# Schematic.net
KiCad netlist of a schematic drawn in EAGLE
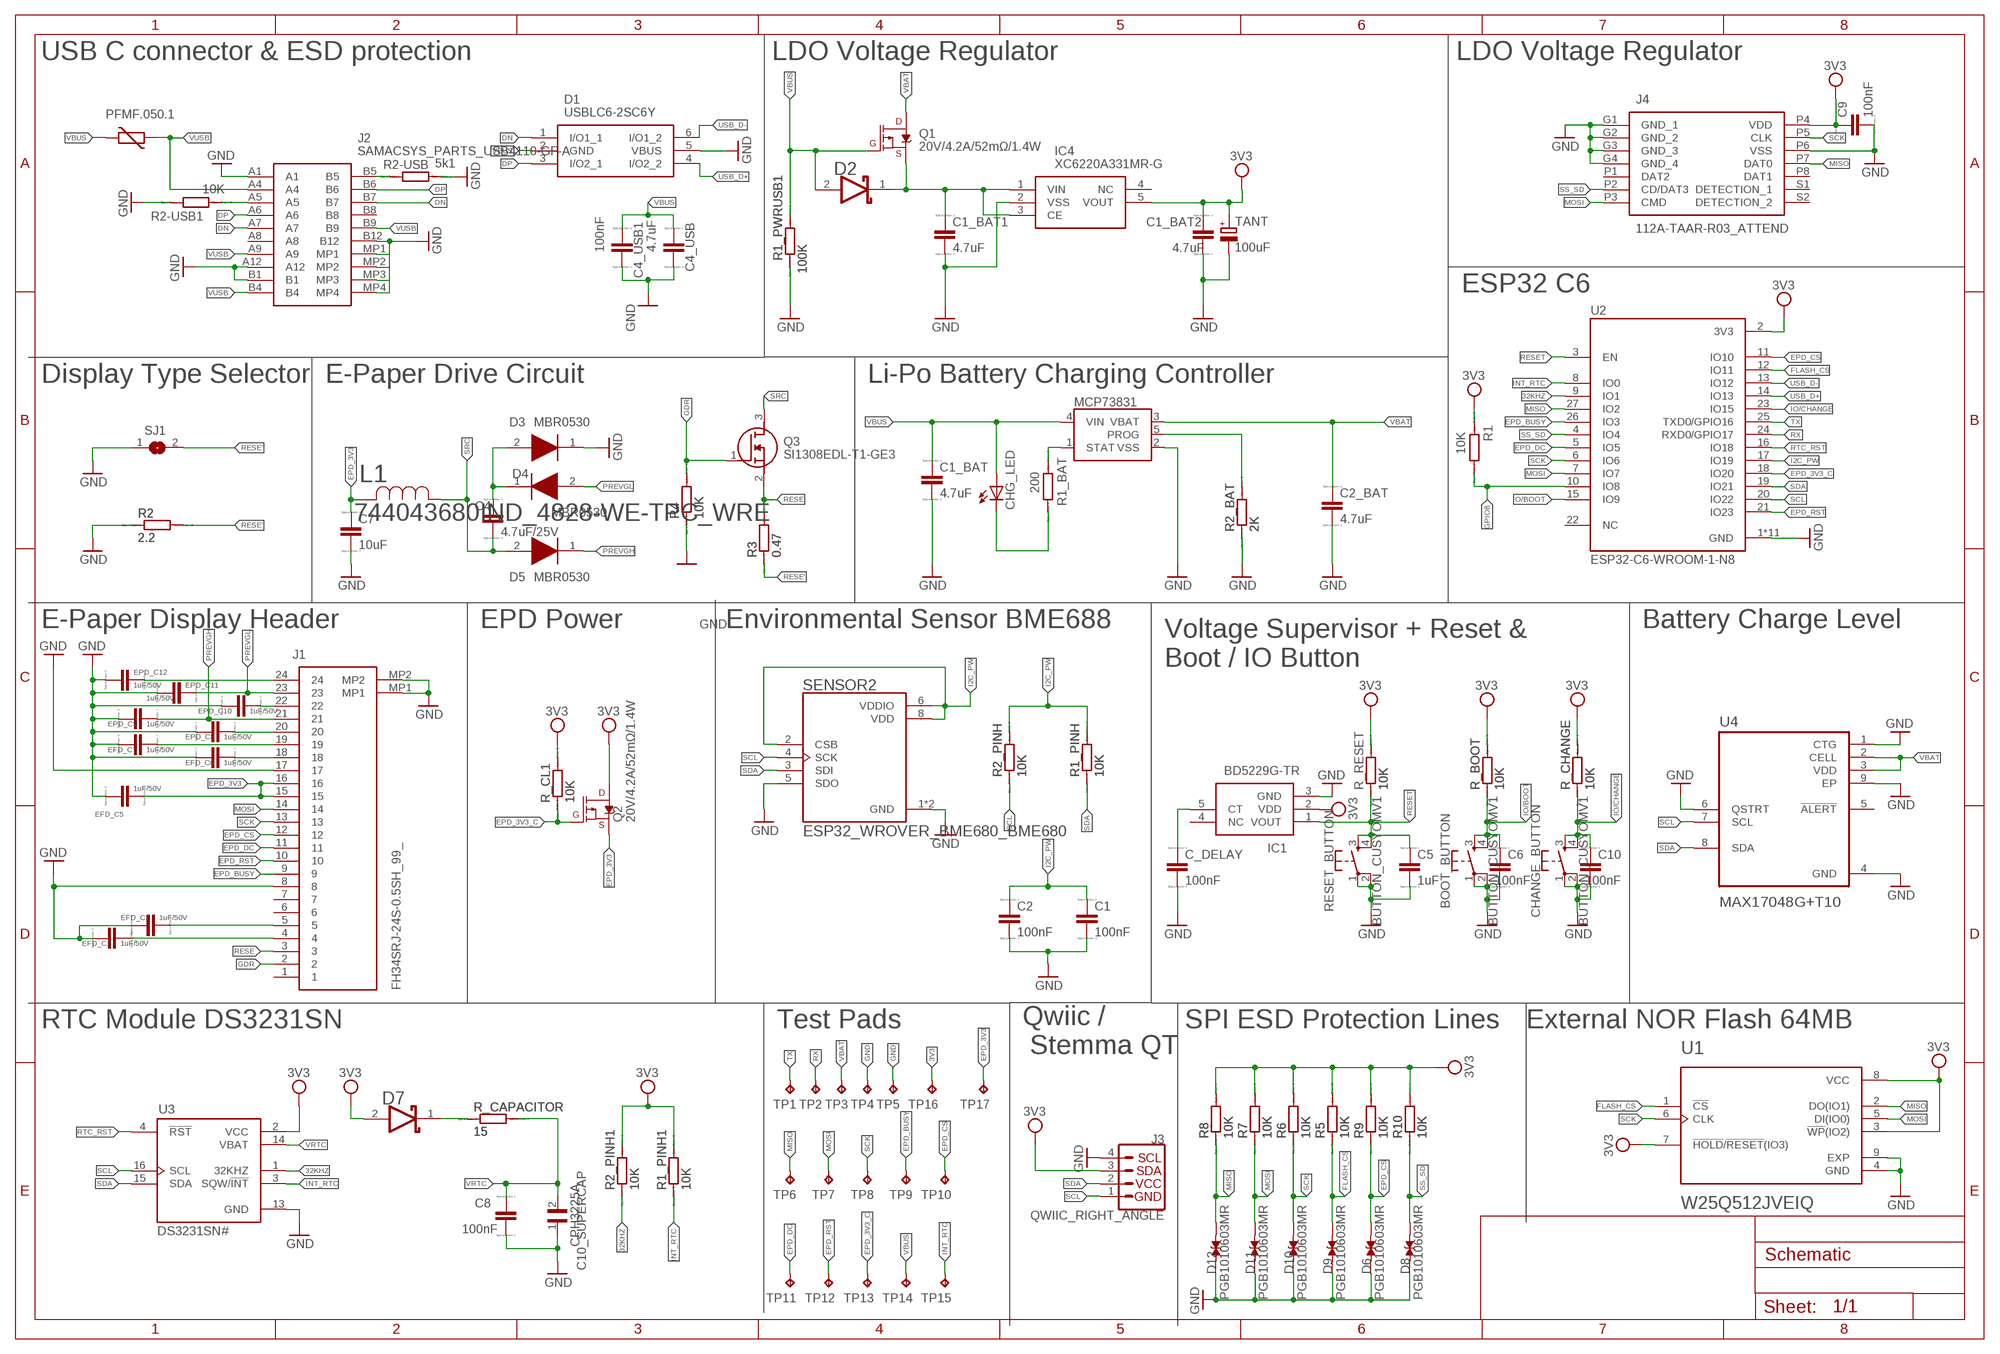
[diagram p0: schematic, sheet 1]

(export (version "E")
  (design (tool "Eeschema 10.0.6"))
  (components
    (comp (ref "BOOT_BUTTON")
      (value "BUTTON_CUSYOMV1")
      (footprint "eagle-import:MYBUTTON")
      (libsource (lib "eagle-import") (part "BUTTON_CUSYOMV1"))
    )
    (comp (ref "C1")
      (value "100nF")
      (footprint "eagle-import:EAGLE-LTSPICE_C0402")
      (libsource (lib "eagle-import") (part "EAGLE-LTSPICE_CC0402"))
    )
    (comp (ref "C1_BAT")
      (value "4.7uF")
      (footprint "eagle-import:EAGLE-LTSPICE_C0402")
      (libsource (lib "eagle-import") (part "EAGLE-LTSPICE_CC0402"))
    )
    (comp (ref "C1_BAT1")
      (value "4.7uF")
      (footprint "eagle-import:EAGLE-LTSPICE_C0402")
      (libsource (lib "eagle-import") (part "EAGLE-LTSPICE_CC0402"))
    )
    (comp (ref "C1_BAT2")
      (value "4.7uF")
      (footprint "eagle-import:EAGLE-LTSPICE_C0402")
      (libsource (lib "eagle-import") (part "EAGLE-LTSPICE_CC0402"))
    )
    (comp (ref "C2")
      (value "100nF")
      (footprint "eagle-import:EAGLE-LTSPICE_C0402")
      (libsource (lib "eagle-import") (part "EAGLE-LTSPICE_CC0402"))
    )
    (comp (ref "C2_BAT")
      (value "4.7uF")
      (footprint "eagle-import:EAGLE-LTSPICE_C0402")
      (libsource (lib "eagle-import") (part "EAGLE-LTSPICE_CC0402"))
    )
    (comp (ref "C4")
      (value "4.7uF/25V")
      (footprint "eagle-import:EAGLE-LTSPICE_C0402")
      (libsource (lib "eagle-import") (part "EAGLE-LTSPICE_CC0402"))
    )
    (comp (ref "C4_USB")
      (value "4.7uF")
      (footprint "eagle-import:EAGLE-LTSPICE_C0402")
      (libsource (lib "eagle-import") (part "EAGLE-LTSPICE_CC0402"))
    )
    (comp (ref "C4_USB1")
      (value "100nF")
      (footprint "eagle-import:EAGLE-LTSPICE_C0402")
      (libsource (lib "eagle-import") (part "EAGLE-LTSPICE_CC0402"))
    )
    (comp (ref "C5")
      (value "1uF")
      (footprint "eagle-import:EAGLE-LTSPICE_C0402")
      (libsource (lib "eagle-import") (part "EAGLE-LTSPICE_CC0402"))
    )
    (comp (ref "C6")
      (value "100nF")
      (footprint "eagle-import:EAGLE-LTSPICE_C0402")
      (libsource (lib "eagle-import") (part "EAGLE-LTSPICE_CC0402"))
    )
    (comp (ref "C7")
      (value "10uF")
      (footprint "eagle-import:EAGLE-LTSPICE_C0402")
      (libsource (lib "eagle-import") (part "EAGLE-LTSPICE_CC0402"))
    )
    (comp (ref "C8")
      (value "100nF")
      (footprint "eagle-import:EAGLE-LTSPICE_C0402")
      (libsource (lib "eagle-import") (part "EAGLE-LTSPICE_CC0402"))
    )
    (comp (ref "C9")
      (value "100nF")
      (footprint "eagle-import:EAGLE-LTSPICE_C0402")
      (libsource (lib "eagle-import") (part "EAGLE-LTSPICE_CC0402"))
    )
    (comp (ref "C10")
      (value "100nF")
      (footprint "eagle-import:EAGLE-LTSPICE_C0402")
      (libsource (lib "eagle-import") (part "EAGLE-LTSPICE_CC0402"))
    )
    (comp (ref "C10_SUPERCAP")
      (value "CPH3225A")
      (footprint "eagle-import:CAPCP3225X100N")
      (fields (field (name "MF") "Seiko Instruments"))
      (libsource (lib "eagle-import") (part "CPH3225A"))
    )
    (comp (ref "CHANGE_BUTTON")
      (value "BUTTON_CUSYOMV1")
      (footprint "eagle-import:MYBUTTON")
      (libsource (lib "eagle-import") (part "BUTTON_CUSYOMV1"))
    )
    (comp (ref "CHG_LED")
      (value "ADAFRUIT_LEDCHIP-LED0603")
      (footprint "eagle-import:ADAFRUIT_CHIP-LED0603")
      (libsource (lib "eagle-import") (part "ADAFRUIT_LEDCHIP-LED0603"))
    )
    (comp (ref "C_DELAY")
      (value "100nF")
      (footprint "eagle-import:EAGLE-LTSPICE_C0402")
      (libsource (lib "eagle-import") (part "EAGLE-LTSPICE_CC0402"))
    )
    (comp (ref "D1")
      (value "USBLC6-2SC6Y")
      (footprint "eagle-import:SOT95P280X145-6N")
      (fields (field (name "MF") "STMicroelectronics"))
      (libsource (lib "eagle-import") (part "USBLC6-2SC6Y"))
    )
    (comp (ref "D2")
      (value "ESP32_WROVER_AVX---SD0805S020S1R0_AVX_SD0805S020S1R0_0_0AVX_SD0805S020S1R0_0_0")
      (footprint "eagle-import:ESP32_WROVER_AVX---SD0805S020S1R0_AVX_SD0805S020S1R0_0")
      (fields
        (field (name "DIGIKEY_PART_NUMBER") "478-7800-1-ND")
        (field (name "MF") "AVX")
        (field (name "MOUSER_PART_NUMBER") "581-SD0805S020S1R0")
      )
      (libsource (lib "eagle-import") (part "ESP32_WROVER_AVX---SD0805S020S1R0_AVX_SD0805S020S1R0_0_0AVX_SD0805S020S1R0_0_0"))
    )
    (comp (ref "D3")
      (value "MBR0530")
      (footprint "eagle-import:SOD3716X135N")
      (fields (field (name "MF") "ON Semiconductor"))
      (libsource (lib "eagle-import") (part "MBR0530"))
    )
    (comp (ref "D4")
      (value "MBR0530")
      (footprint "eagle-import:SOD3716X135N")
      (fields (field (name "MF") "ON Semiconductor"))
      (libsource (lib "eagle-import") (part "MBR0530"))
    )
    (comp (ref "D5")
      (value "MBR0530")
      (footprint "eagle-import:SOD3716X135N")
      (fields (field (name "MF") "ON Semiconductor"))
      (libsource (lib "eagle-import") (part "MBR0530"))
    )
    (comp (ref "D6")
      (value "PGB1010603MR")
      (footprint "eagle-import:DIOC1608X36N")
      (fields (field (name "MF") "Littelfuse Inc."))
      (libsource (lib "eagle-import") (part "PGB1010603MR"))
    )
    (comp (ref "D7")
      (value "ESP32_WROVER_AVX---SD0805S020S1R0_AVX_SD0805S020S1R0_0_0AVX_SD0805S020S1R0_0_0")
      (footprint "eagle-import:ESP32_WROVER_AVX---SD0805S020S1R0_AVX_SD0805S020S1R0_0")
      (fields
        (field (name "DIGIKEY_PART_NUMBER") "478-7800-1-ND")
        (field (name "MF") "AVX")
        (field (name "MOUSER_PART_NUMBER") "581-SD0805S020S1R0")
      )
      (libsource (lib "eagle-import") (part "ESP32_WROVER_AVX---SD0805S020S1R0_AVX_SD0805S020S1R0_0_0AVX_SD0805S020S1R0_0_0"))
    )
    (comp (ref "D8")
      (value "PGB1010603MR")
      (footprint "eagle-import:DIOC1608X36N")
      (fields (field (name "MF") "Littelfuse Inc."))
      (libsource (lib "eagle-import") (part "PGB1010603MR"))
    )
    (comp (ref "D9")
      (value "PGB1010603MR")
      (footprint "eagle-import:DIOC1608X36N")
      (fields (field (name "MF") "Littelfuse Inc."))
      (libsource (lib "eagle-import") (part "PGB1010603MR"))
    )
    (comp (ref "D10")
      (value "PGB1010603MR")
      (footprint "eagle-import:DIOC1608X36N")
      (fields (field (name "MF") "Littelfuse Inc."))
      (libsource (lib "eagle-import") (part "PGB1010603MR"))
    )
    (comp (ref "D11")
      (value "PGB1010603MR")
      (footprint "eagle-import:DIOC1608X36N")
      (fields (field (name "MF") "Littelfuse Inc."))
      (libsource (lib "eagle-import") (part "PGB1010603MR"))
    )
    (comp (ref "D12")
      (value "PGB1010603MR")
      (footprint "eagle-import:DIOC1608X36N")
      (fields (field (name "MF") "Littelfuse Inc."))
      (libsource (lib "eagle-import") (part "PGB1010603MR"))
    )
    (comp (ref "EFD_C1")
      (value "1uF/50V")
      (footprint "eagle-import:EAGLE-LTSPICE_C0402")
      (libsource (lib "eagle-import") (part "EAGLE-LTSPICE_CC0402"))
    )
    (comp (ref "EFD_C2")
      (value "1uF/50V")
      (footprint "eagle-import:EAGLE-LTSPICE_C0402")
      (libsource (lib "eagle-import") (part "EAGLE-LTSPICE_CC0402"))
    )
    (comp (ref "EFD_C5")
      (value "1uF/50V")
      (footprint "eagle-import:EAGLE-LTSPICE_C0402")
      (libsource (lib "eagle-import") (part "EAGLE-LTSPICE_CC0402"))
    )
    (comp (ref "EFD_C6")
      (value "1uF/50V")
      (footprint "eagle-import:EAGLE-LTSPICE_C0402")
      (libsource (lib "eagle-import") (part "EAGLE-LTSPICE_CC0402"))
    )
    (comp (ref "EFD_C7")
      (value "1uF/50V")
      (footprint "eagle-import:EAGLE-LTSPICE_C0402")
      (libsource (lib "eagle-import") (part "EAGLE-LTSPICE_CC0402"))
    )
    (comp (ref "EPD_C8")
      (value "1uF/50V")
      (footprint "eagle-import:EAGLE-LTSPICE_C0402")
      (libsource (lib "eagle-import") (part "EAGLE-LTSPICE_CC0402"))
    )
    (comp (ref "EPD_C9")
      (value "1uF/50V")
      (footprint "eagle-import:EAGLE-LTSPICE_C0402")
      (libsource (lib "eagle-import") (part "EAGLE-LTSPICE_CC0402"))
    )
    (comp (ref "EPD_C10")
      (value "1uF/50V")
      (footprint "eagle-import:EAGLE-LTSPICE_C0402")
      (libsource (lib "eagle-import") (part "EAGLE-LTSPICE_CC0402"))
    )
    (comp (ref "EPD_C11")
      (value "1uF/50V")
      (footprint "eagle-import:EAGLE-LTSPICE_C0402")
      (libsource (lib "eagle-import") (part "EAGLE-LTSPICE_CC0402"))
    )
    (comp (ref "EPD_C12")
      (value "1uF/50V")
      (footprint "eagle-import:EAGLE-LTSPICE_C0402")
      (libsource (lib "eagle-import") (part "EAGLE-LTSPICE_CC0402"))
    )
    (comp (ref "IC1")
      (value "BD5229G-TR")
      (footprint "eagle-import:SOT95P280X125-5N")
      (fields (field (name "MOUSER_PART_NUMBER") "755-BD5229G-TR"))
      (libsource (lib "eagle-import") (part "BD5229G-TR"))
    )
    (comp (ref "IC4")
      (value "XC6220A331MR-G")
      (footprint "eagle-import:SOT95P280X120-5N")
      (fields (field (name "MOUSER_PART_NUMBER") "865-XC6220A331MR-G"))
      (libsource (lib "eagle-import") (part "XC6220A331MR-G"))
    )
    (comp (ref "J1")
      (value "FH34SRJ-24S-0.5SH_99_")
      (footprint "eagle-import:FH34SRJ24S05SH99")
      (fields
        (field (name "MANUFACTURER_PART_NUMBER") "FH34SRJ-24S-0.5SH(99)")
        (field (name "MOUSER_PART_NUMBER") "798-FH34SRJ24S05SH99")
      )
      (libsource (lib "eagle-import") (part "FH34SRJ-24S-0.5SH_99_"))
    )
    (comp (ref "J2")
      (value "SAMACSYS_PARTS_USB4110-GF-A")
      (footprint "eagle-import:SAMACSYS_PARTS_USB4110GFA")
      (fields
        (field (name "MANUFACTURER_PART_NUMBER") "USB4110-GF-A")
        (field (name "MOUSER_PART_NUMBER") "640-USB4110-GF-A")
      )
      (libsource (lib "eagle-import") (part "SAMACSYS_PARTS_USB4110-GF-A"))
    )
    (comp (ref "J3")
      (value "QWIIC_RIGHT_ANGLE")
      (footprint "eagle-import:JST04_1MM_RA")
      (libsource (lib "eagle-import") (part "QWIIC_CONNECTORJS-1MM"))
    )
    (comp (ref "J4")
      (value "112A-TAAR-R03_ATTEND")
      (footprint "eagle-import:112ATAARR03ATTEND")
      (fields (field (name "MANUFACTURER_PART_NUMBER") "112A-TAAR-R03 ATTEND"))
      (libsource (lib "eagle-import") (part "112A-TAAR-R03_ATTEND"))
    )
    (comp (ref "L1")
      (value "744043680IND_4828-WE-TPC_WRE")
      (footprint "eagle-import:IND_4828-WE-TPC_WRE")
      (fields
        (field (name "MANUFACTURER_PART_NUMBER") "744043680")
        (field (name "COPYRIGHT") "Copyright (C) 2024 Ultra Librarian. All rights reserved.")
      )
      (libsource (lib "eagle-import") (part "744043680IND_4828-WE-TPC_WRE"))
    )
    (comp (ref "MCP73831")
      (value "ESP32_WROVER_SPARKFUN-IC-POWER_MCP73831")
      (footprint "eagle-import:ESP32_WROVER_SPARKFUN-IC-POWER_SOT23-5")
      (libsource (lib "eagle-import") (part "ESP32_WROVER_SPARKFUN-IC-POWER_MCP73831"))
    )
    (comp (ref "PFMF.050.1")
      (value "ESP32C6_VARISTORCN1812")
      (footprint "eagle-import:ESP32C6_VARISTOR_CT_CN1812")
      (libsource (lib "eagle-import") (part "ESP32C6_VARISTORCN1812"))
    )
    (comp (ref "Q1")
      (value "20V/4.2A/52mΩ/1.4W")
      (footprint "eagle-import:ESP32_WROVER_SPARKFUN-DISCRETESEMI_SOT23-3")
      (libsource (lib "eagle-import") (part "ESP32_WROVER_SPARKFUN-DISCRETESEMI_MOSFET_PCH-DMG2305UX-7"))
    )
    (comp (ref "Q2")
      (value "20V/4.2A/52mΩ/1.4W")
      (footprint "eagle-import:ESP32_WROVER_SPARKFUN-DISCRETESEMI_SOT23-3")
      (libsource (lib "eagle-import") (part "ESP32_WROVER_SPARKFUN-DISCRETESEMI_MOSFET_PCH-DMG2305UX-7"))
    )
    (comp (ref "Q3")
      (value "SI1308EDL-T1-GE3")
      (footprint "eagle-import:SOT65P210X110-3N")
      (fields (field (name "MF") "Vishay Siliconix"))
      (libsource (lib "eagle-import") (part "SI1308EDL-T1-GE3"))
    )
    (comp (ref "R1")
      (value "10K")
      (footprint "eagle-import:ESP32_WROVER_EAGLE-LTSPICE_R0402")
      (libsource (lib "eagle-import") (part "ESP32_WROVER_EAGLE-LTSPICE_RR0402"))
    )
    (comp (ref "R1_BAT")
      (value "200")
      (footprint "eagle-import:ESP32_WROVER_EAGLE-LTSPICE_R0402")
      (libsource (lib "eagle-import") (part "ESP32_WROVER_EAGLE-LTSPICE_RR0402"))
    )
    (comp (ref "R1_PINH")
      (value "10K")
      (footprint "eagle-import:ESP32_WROVER_EAGLE-LTSPICE_R0402")
      (libsource (lib "eagle-import") (part "ESP32_WROVER_EAGLE-LTSPICE_RR0402"))
    )
    (comp (ref "R1_PINH1")
      (value "10K")
      (footprint "eagle-import:ESP32_WROVER_EAGLE-LTSPICE_R0402")
      (libsource (lib "eagle-import") (part "ESP32_WROVER_EAGLE-LTSPICE_RR0402"))
    )
    (comp (ref "R1_PWRUSB1")
      (value "100K")
      (footprint "eagle-import:ESP32_WROVER_EAGLE-LTSPICE_R0402")
      (libsource (lib "eagle-import") (part "ESP32_WROVER_EAGLE-LTSPICE_RR0402"))
    )
    (comp (ref "R2")
      (value "2.2")
      (footprint "eagle-import:ESP32_WROVER_EAGLE-LTSPICE_R0402")
      (libsource (lib "eagle-import") (part "ESP32_WROVER_EAGLE-LTSPICE_RR0402"))
    )
    (comp (ref "R2-USB")
      (value "5k1")
      (footprint "eagle-import:ESP32_WROVER_EAGLE-LTSPICE_R0402")
      (libsource (lib "eagle-import") (part "ESP32_WROVER_EAGLE-LTSPICE_RR0402"))
    )
    (comp (ref "R2-USB1")
      (value "10K")
      (footprint "eagle-import:ESP32_WROVER_EAGLE-LTSPICE_R0402")
      (libsource (lib "eagle-import") (part "ESP32_WROVER_EAGLE-LTSPICE_RR0402"))
    )
    (comp (ref "R2_BAT")
      (value "2K")
      (footprint "eagle-import:ESP32_WROVER_EAGLE-LTSPICE_R0402")
      (libsource (lib "eagle-import") (part "ESP32_WROVER_EAGLE-LTSPICE_RR0402"))
    )
    (comp (ref "R2_PINH")
      (value "10K")
      (footprint "eagle-import:ESP32_WROVER_EAGLE-LTSPICE_R0402")
      (libsource (lib "eagle-import") (part "ESP32_WROVER_EAGLE-LTSPICE_RR0402"))
    )
    (comp (ref "R2_PINH1")
      (value "10K")
      (footprint "eagle-import:ESP32_WROVER_EAGLE-LTSPICE_R0402")
      (libsource (lib "eagle-import") (part "ESP32_WROVER_EAGLE-LTSPICE_RR0402"))
    )
    (comp (ref "R3")
      (value "0.47")
      (footprint "eagle-import:ESP32_WROVER_EAGLE-LTSPICE_R0402")
      (libsource (lib "eagle-import") (part "ESP32_WROVER_EAGLE-LTSPICE_RR0402"))
    )
    (comp (ref "R4")
      (value "10K")
      (footprint "eagle-import:ESP32_WROVER_EAGLE-LTSPICE_R0402")
      (libsource (lib "eagle-import") (part "ESP32_WROVER_EAGLE-LTSPICE_RR0402"))
    )
    (comp (ref "R5")
      (value "10K")
      (footprint "eagle-import:ESP32_WROVER_EAGLE-LTSPICE_R0402")
      (libsource (lib "eagle-import") (part "ESP32_WROVER_EAGLE-LTSPICE_RR0402"))
    )
    (comp (ref "R6")
      (value "10K")
      (footprint "eagle-import:ESP32_WROVER_EAGLE-LTSPICE_R0402")
      (libsource (lib "eagle-import") (part "ESP32_WROVER_EAGLE-LTSPICE_RR0402"))
    )
    (comp (ref "R7")
      (value "10K")
      (footprint "eagle-import:ESP32_WROVER_EAGLE-LTSPICE_R0402")
      (libsource (lib "eagle-import") (part "ESP32_WROVER_EAGLE-LTSPICE_RR0402"))
    )
    (comp (ref "R8")
      (value "10K")
      (footprint "eagle-import:ESP32_WROVER_EAGLE-LTSPICE_R0402")
      (libsource (lib "eagle-import") (part "ESP32_WROVER_EAGLE-LTSPICE_RR0402"))
    )
    (comp (ref "R9")
      (value "10K")
      (footprint "eagle-import:ESP32_WROVER_EAGLE-LTSPICE_R0402")
      (libsource (lib "eagle-import") (part "ESP32_WROVER_EAGLE-LTSPICE_RR0402"))
    )
    (comp (ref "R10")
      (value "10K")
      (footprint "eagle-import:ESP32_WROVER_EAGLE-LTSPICE_R0402")
      (libsource (lib "eagle-import") (part "ESP32_WROVER_EAGLE-LTSPICE_RR0402"))
    )
    (comp (ref "RESET_BUTTON")
      (value "BUTTON_CUSYOMV1")
      (footprint "eagle-import:MYBUTTON")
      (libsource (lib "eagle-import") (part "BUTTON_CUSYOMV1"))
    )
    (comp (ref "R_BOOT")
      (value "10K")
      (footprint "eagle-import:ESP32_WROVER_EAGLE-LTSPICE_R0402")
      (libsource (lib "eagle-import") (part "ESP32_WROVER_EAGLE-LTSPICE_RR0402"))
    )
    (comp (ref "R_CAPACITOR")
      (value "15")
      (footprint "eagle-import:ESP32_WROVER_EAGLE-LTSPICE_R0402")
      (libsource (lib "eagle-import") (part "ESP32_WROVER_EAGLE-LTSPICE_RR0402"))
    )
    (comp (ref "R_CHANGE")
      (value "10K")
      (footprint "eagle-import:ESP32_WROVER_EAGLE-LTSPICE_R0402")
      (libsource (lib "eagle-import") (part "ESP32_WROVER_EAGLE-LTSPICE_RR0402"))
    )
    (comp (ref "R_CL1")
      (value "10K")
      (footprint "eagle-import:ESP32_WROVER_EAGLE-LTSPICE_R0402")
      (libsource (lib "eagle-import") (part "ESP32_WROVER_EAGLE-LTSPICE_RR0402"))
    )
    (comp (ref "R_RESET")
      (value "10K")
      (footprint "eagle-import:ESP32_WROVER_EAGLE-LTSPICE_R0402")
      (libsource (lib "eagle-import") (part "ESP32_WROVER_EAGLE-LTSPICE_RR0402"))
    )
    (comp (ref "SENSOR2")
      (value "ESP32_WROVER_BME680_BME680")
      (footprint "eagle-import:ESP32_WROVER_BME680_PSON80P300X300X100-8N")
      (fields (field (name "MF") "Bosch Sensortec") (field (name "MP") "BME680"))
      (libsource (lib "eagle-import") (part "ESP32_WROVER_BME680_BME680"))
    )
    (comp (ref "SJ1") (value "SJ") (footprint "eagle-import:SJ") (libsource (lib "eagle-import") (part "SJ")))
    (comp (ref "TANT")
      (value "100uF")
      (footprint "eagle-import:RCL_CT3528")
      (libsource (lib "eagle-import") (part "RCL_CPOL-EUCT3528"))
    )
    (comp (ref "TP1")
      (value "TPTP20R")
      (footprint "eagle-import:TP20R")
      (libsource (lib "eagle-import") (part "TPTP20R"))
    )
    (comp (ref "TP2")
      (value "TPTP20R")
      (footprint "eagle-import:TP20R")
      (libsource (lib "eagle-import") (part "TPTP20R"))
    )
    (comp (ref "TP3")
      (value "TPTP20R")
      (footprint "eagle-import:TP20R")
      (libsource (lib "eagle-import") (part "TPTP20R"))
    )
    (comp (ref "TP4")
      (value "TPTP20R")
      (footprint "eagle-import:TP20R")
      (libsource (lib "eagle-import") (part "TPTP20R"))
    )
    (comp (ref "TP5")
      (value "TPTP20R")
      (footprint "eagle-import:TP20R")
      (libsource (lib "eagle-import") (part "TPTP20R"))
    )
    (comp (ref "TP6")
      (value "TPTP20R")
      (footprint "eagle-import:TP20R")
      (libsource (lib "eagle-import") (part "TPTP20R"))
    )
    (comp (ref "TP7")
      (value "TPTP20R")
      (footprint "eagle-import:TP20R")
      (libsource (lib "eagle-import") (part "TPTP20R"))
    )
    (comp (ref "TP8")
      (value "TPTP20R")
      (footprint "eagle-import:TP20R")
      (libsource (lib "eagle-import") (part "TPTP20R"))
    )
    (comp (ref "TP9")
      (value "TPTP20R")
      (footprint "eagle-import:TP20R")
      (libsource (lib "eagle-import") (part "TPTP20R"))
    )
    (comp (ref "TP10")
      (value "TPTP20R")
      (footprint "eagle-import:TP20R")
      (libsource (lib "eagle-import") (part "TPTP20R"))
    )
    (comp (ref "TP11")
      (value "TPTP20R")
      (footprint "eagle-import:TP20R")
      (libsource (lib "eagle-import") (part "TPTP20R"))
    )
    (comp (ref "TP12")
      (value "TPTP20R")
      (footprint "eagle-import:TP20R")
      (libsource (lib "eagle-import") (part "TPTP20R"))
    )
    (comp (ref "TP13")
      (value "TPTP20R")
      (footprint "eagle-import:TP20R")
      (libsource (lib "eagle-import") (part "TPTP20R"))
    )
    (comp (ref "TP14")
      (value "TPTP20R")
      (footprint "eagle-import:TP20R")
      (libsource (lib "eagle-import") (part "TPTP20R"))
    )
    (comp (ref "TP15")
      (value "TPTP20R")
      (footprint "eagle-import:TP20R")
      (libsource (lib "eagle-import") (part "TPTP20R"))
    )
    (comp (ref "TP16")
      (value "TPTP20R")
      (footprint "eagle-import:TP20R")
      (libsource (lib "eagle-import") (part "TPTP20R"))
    )
    (comp (ref "TP17")
      (value "TPTP20R")
      (footprint "eagle-import:TP20R")
      (libsource (lib "eagle-import") (part "TPTP20R"))
    )
    (comp (ref "U1")
      (value "W25Q512JVEIQ")
      (footprint "eagle-import:SON127P600X800X80-9N")
      (fields (field (name "MF") "Winbond Electronics"))
      (libsource (lib "eagle-import") (part "W25Q512JVEIQ"))
    )
    (comp (ref "U2")
      (value "ESP32-C6-WROOM-1-N8")
      (footprint "eagle-import:XCVR_ESP32-C6-WROOM-1-N8")
      (fields (field (name "MF") "Espressif Systems"))
      (libsource (lib "eagle-import") (part "ESP32-C6-WROOM-1-N8"))
    )
    (comp (ref "U3")
      (value "DS3231SN#")
      (footprint "eagle-import:SOIC127P1032X265-16N")
      (fields (field (name "MF") "Analog Devices"))
      (libsource (lib "eagle-import") (part "DS3231SN#"))
    )
    (comp (ref "U4")
      (value "MAX17048G+T10")
      (footprint "eagle-import:SON50P200X200X80-9N")
      (fields (field (name "MF") "Analog Devices"))
      (libsource (lib "eagle-import") (part "MAX17048G+T10"))
    )
  )
  (nets
    (net (code "1") (name "3V3") (class "Default")
      (node (ref "C1_BAT2") (pin "1") (pinfunction "1_1") (pintype "passive"))
      (node (ref "C9") (pin "1") (pinfunction "1_1") (pintype "passive"))
      (node (ref "D7") (pin "2") (pinfunction "ANODE_2") (pintype "bidirectional"))
      (node (ref "IC1") (pin "2") (pinfunction "VDD_2") (pintype "bidirectional"))
      (node (ref "IC4") (pin "5") (pinfunction "VOUT_5") (pintype "bidirectional"))
      (node (ref "J3") (pin "3") (pinfunction "3_3") (pintype "passive"))
      (node (ref "J4") (pin "P4") (pinfunction "VDD_P4") (pintype "bidirectional"))
      (node (ref "Q2") (pin "3") (pinfunction "D_3") (pintype "bidirectional"))
      (node (ref "R1") (pin "2") (pinfunction "2_2") (pintype "passive"))
      (node (ref "R10") (pin "2") (pinfunction "2_2") (pintype "passive"))
      (node (ref "R1_PINH1") (pin "2") (pinfunction "2_2") (pintype "passive"))
      (node (ref "R2_PINH1") (pin "2") (pinfunction "2_2") (pintype "passive"))
      (node (ref "R5") (pin "2") (pinfunction "2_2") (pintype "passive"))
      (node (ref "R6") (pin "2") (pinfunction "2_2") (pintype "passive"))
      (node (ref "R7") (pin "2") (pinfunction "2_2") (pintype "passive"))
      (node (ref "R8") (pin "2") (pinfunction "2_2") (pintype "passive"))
      (node (ref "R9") (pin "2") (pinfunction "2_2") (pintype "passive"))
      (node (ref "R_BOOT") (pin "2") (pinfunction "2_2") (pintype "passive"))
      (node (ref "R_CHANGE") (pin "2") (pinfunction "2_2") (pintype "passive"))
      (node (ref "R_CL1") (pin "2") (pinfunction "2_2") (pintype "passive"))
      (node (ref "R_RESET") (pin "2") (pinfunction "2_2") (pintype "passive"))
      (node (ref "TANT") (pin "+") (pinfunction "+_+") (pintype "passive"))
      (node (ref "TP16") (pin "TP") (pinfunction "TP_TP") (pintype "input"))
      (node (ref "U1") (pin "3") (pinfunction "~{WP}(IO2)_3") (pintype "bidirectional"))
      (node (ref "U1") (pin "7") (pinfunction "~{HOLD}/~{RESET}(IO3)_7") (pintype "bidirectional"))
      (node (ref "U1") (pin "8") (pinfunction "VCC_8") (pintype "power_in"))
      (node (ref "U2") (pin "2") (pinfunction "3V3_2") (pintype "power_in"))
      (node (ref "U3") (pin "2") (pinfunction "VCC_2") (pintype "power_in"))
    )
    (net (code "2") (name "32KHZ") (class "Default")
      (node (ref "R2_PINH1") (pin "1") (pinfunction "1_1") (pintype "passive"))
      (node (ref "U2") (pin "9") (pinfunction "IO1_9") (pintype "bidirectional"))
      (node (ref "U3") (pin "1") (pinfunction "32KHZ_1") (pintype "output"))
    )
    (net (code "3") (name "DN") (class "Default")
      (node (ref "D1") (pin "1") (pinfunction "I/O1_1_1") (pintype "bidirectional"))
      (node (ref "J2") (pin "A7") (pinfunction "A7_A7") (pintype "bidirectional"))
      (node (ref "J2") (pin "B7") (pinfunction "B7_B7") (pintype "bidirectional"))
    )
    (net (code "4") (name "DP") (class "Default")
      (node (ref "D1") (pin "3") (pinfunction "I/O2_1_3") (pintype "bidirectional"))
      (node (ref "J2") (pin "A6") (pinfunction "A6_A6") (pintype "bidirectional"))
      (node (ref "J2") (pin "B6") (pinfunction "B6_B6") (pintype "bidirectional"))
    )
    (net (code "5") (name "EPD_3V3") (class "Default")
      (node (ref "C7") (pin "1") (pinfunction "1_1") (pintype "passive"))
      (node (ref "EFD_C5") (pin "1") (pinfunction "1_1") (pintype "passive"))
      (node (ref "J1") (pin "15") (pinfunction "15_15") (pintype "bidirectional"))
      (node (ref "J1") (pin "16") (pinfunction "16_16") (pintype "bidirectional"))
      (node (ref "L1") (pin "2") (pinfunction "2_2") (pintype "passive"))
      (node (ref "Q2") (pin "2") (pinfunction "S_2") (pintype "bidirectional"))
      (node (ref "TP17") (pin "TP") (pinfunction "TP_TP") (pintype "input"))
    )
    (net (code "6") (name "EPD_3V3_C") (class "Default")
      (node (ref "Q2") (pin "1") (pinfunction "G_1") (pintype "bidirectional"))
      (node (ref "R_CL1") (pin "1") (pinfunction "1_1") (pintype "passive"))
      (node (ref "TP13") (pin "TP") (pinfunction "TP_TP") (pintype "input"))
      (node (ref "U2") (pin "18") (pinfunction "IO20_18") (pintype "bidirectional"))
    )
    (net (code "7") (name "EPD_BUSY") (class "Default")
      (node (ref "J1") (pin "9") (pinfunction "9_9") (pintype "bidirectional"))
      (node (ref "TP9") (pin "TP") (pinfunction "TP_TP") (pintype "input"))
      (node (ref "U2") (pin "26") (pinfunction "IO3_26") (pintype "bidirectional"))
    )
    (net (code "8") (name "EPD_CS") (class "Default")
      (node (ref "D6") (pin "2") (pinfunction "2_2") (pintype "passive"))
      (node (ref "J1") (pin "12") (pinfunction "12_12") (pintype "bidirectional"))
      (node (ref "R9") (pin "1") (pinfunction "1_1") (pintype "passive"))
      (node (ref "TP10") (pin "TP") (pinfunction "TP_TP") (pintype "input"))
      (node (ref "U2") (pin "11") (pinfunction "IO10_11") (pintype "bidirectional"))
    )
    (net (code "9") (name "EPD_DC") (class "Default")
      (node (ref "J1") (pin "11") (pinfunction "11_11") (pintype "bidirectional"))
      (node (ref "TP11") (pin "TP") (pinfunction "TP_TP") (pintype "input"))
      (node (ref "U2") (pin "5") (pinfunction "IO5_5") (pintype "bidirectional"))
    )
    (net (code "10") (name "EPD_RST") (class "Default")
      (node (ref "J1") (pin "10") (pinfunction "10_10") (pintype "bidirectional"))
      (node (ref "TP12") (pin "TP") (pinfunction "TP_TP") (pintype "input"))
      (node (ref "U2") (pin "21") (pinfunction "IO23_21") (pintype "bidirectional"))
    )
    (net (code "11") (name "FLASH_CS") (class "Default")
      (node (ref "D9") (pin "2") (pinfunction "2_2") (pintype "passive"))
      (node (ref "R5") (pin "1") (pinfunction "1_1") (pintype "passive"))
      (node (ref "U1") (pin "1") (pinfunction "~{CS}_1") (pintype "input"))
      (node (ref "U2") (pin "12") (pinfunction "IO11_12") (pintype "bidirectional"))
    )
    (net (code "12") (name "GDR") (class "Default")
      (node (ref "J1") (pin "2") (pinfunction "2_2") (pintype "bidirectional"))
      (node (ref "Q3") (pin "1") (pinfunction "G_1") (pintype "bidirectional"))
      (node (ref "R4") (pin "2") (pinfunction "2_2") (pintype "passive"))
    )
    (net (code "13") (name "GND") (class "Default")
      (node (ref "BOOT_BUTTON") (pin "1") (pinfunction "1_1") (pintype "passive"))
      (node (ref "BOOT_BUTTON") (pin "2") (pinfunction "2_2") (pintype "passive"))
      (node (ref "C1") (pin "2") (pinfunction "2_2") (pintype "passive"))
      (node (ref "C10") (pin "2") (pinfunction "2_2") (pintype "passive"))
      (node (ref "C10_SUPERCAP") (pin "1") (pinfunction "1_1") (pintype "passive"))
      (node (ref "C1_BAT") (pin "2") (pinfunction "2_2") (pintype "passive"))
      (node (ref "C1_BAT1") (pin "2") (pinfunction "2_2") (pintype "passive"))
      (node (ref "C1_BAT2") (pin "2") (pinfunction "2_2") (pintype "passive"))
      (node (ref "C2") (pin "2") (pinfunction "2_2") (pintype "passive"))
      (node (ref "C2_BAT") (pin "2") (pinfunction "2_2") (pintype "passive"))
      (node (ref "C4_USB") (pin "2") (pinfunction "2_2") (pintype "passive"))
      (node (ref "C4_USB1") (pin "2") (pinfunction "2_2") (pintype "passive"))
      (node (ref "C5") (pin "2") (pinfunction "2_2") (pintype "passive"))
      (node (ref "C6") (pin "2") (pinfunction "2_2") (pintype "passive"))
      (node (ref "C7") (pin "2") (pinfunction "2_2") (pintype "passive"))
      (node (ref "C8") (pin "2") (pinfunction "2_2") (pintype "passive"))
      (node (ref "C9") (pin "2") (pinfunction "2_2") (pintype "passive"))
      (node (ref "CHANGE_BUTTON") (pin "1") (pinfunction "1_1") (pintype "passive"))
      (node (ref "CHANGE_BUTTON") (pin "2") (pinfunction "2_2") (pintype "passive"))
      (node (ref "C_DELAY") (pin "2") (pinfunction "2_2") (pintype "passive"))
      (node (ref "D1") (pin "5") (pinfunction "VBUS_5") (pintype "bidirectional"))
      (node (ref "D10") (pin "1") (pinfunction "1_1") (pintype "passive"))
      (node (ref "D11") (pin "1") (pinfunction "1_1") (pintype "passive"))
      (node (ref "D12") (pin "1") (pinfunction "1_1") (pintype "passive"))
      (node (ref "D3") (pin "1") (pinfunction "K_1") (pintype "bidirectional"))
      (node (ref "D6") (pin "1") (pinfunction "1_1") (pintype "passive"))
      (node (ref "D8") (pin "1") (pinfunction "1_1") (pintype "passive"))
      (node (ref "D9") (pin "1") (pinfunction "1_1") (pintype "passive"))
      (node (ref "EFD_C1") (pin "2") (pinfunction "2_2") (pintype "passive"))
      (node (ref "EFD_C2") (pin "2") (pinfunction "2_2") (pintype "passive"))
      (node (ref "EFD_C5") (pin "2") (pinfunction "2_2") (pintype "passive"))
      (node (ref "EFD_C6") (pin "2") (pinfunction "2_2") (pintype "passive"))
      (node (ref "EFD_C7") (pin "2") (pinfunction "2_2") (pintype "passive"))
      (node (ref "EPD_C10") (pin "2") (pinfunction "2_2") (pintype "passive"))
      (node (ref "EPD_C11") (pin "2") (pinfunction "2_2") (pintype "passive"))
      (node (ref "EPD_C12") (pin "2") (pinfunction "2_2") (pintype "passive"))
      (node (ref "EPD_C8") (pin "2") (pinfunction "2_2") (pintype "passive"))
      (node (ref "EPD_C9") (pin "2") (pinfunction "2_2") (pintype "passive"))
      (node (ref "IC1") (pin "3") (pinfunction "GND_3") (pintype "bidirectional"))
      (node (ref "IC4") (pin "2") (pinfunction "VSS_2") (pintype "bidirectional"))
      (node (ref "J1") (pin "17") (pinfunction "17_17") (pintype "bidirectional"))
      (node (ref "J1") (pin "8") (pinfunction "8_8") (pintype "bidirectional"))
      (node (ref "J1") (pin "MP1") (pinfunction "MP1_MP1") (pintype "bidirectional"))
      (node (ref "J1") (pin "MP2") (pinfunction "MP2_MP2") (pintype "bidirectional"))
      (node (ref "J2") (pin "A1") (pinfunction "A1_A1") (pintype "bidirectional"))
      (node (ref "J2") (pin "A12") (pinfunction "A12_A12") (pintype "bidirectional"))
      (node (ref "J2") (pin "B1") (pinfunction "B1_B1") (pintype "bidirectional"))
      (node (ref "J2") (pin "B12") (pinfunction "B12_B12") (pintype "bidirectional"))
      (node (ref "J2") (pin "MP1") (pinfunction "MP1_MP1") (pintype "bidirectional"))
      (node (ref "J2") (pin "MP2") (pinfunction "MP2_MP2") (pintype "bidirectional"))
      (node (ref "J2") (pin "MP3") (pinfunction "MP3_MP3") (pintype "bidirectional"))
      (node (ref "J2") (pin "MP4") (pinfunction "MP4_MP4") (pintype "bidirectional"))
      (node (ref "J3") (pin "4") (pinfunction "4_4") (pintype "passive"))
      (node (ref "J4") (pin "G1") (pinfunction "GND_1_G1") (pintype "bidirectional"))
      (node (ref "J4") (pin "G2") (pinfunction "GND_2_G2") (pintype "bidirectional"))
      (node (ref "J4") (pin "G3") (pinfunction "GND_3_G3") (pintype "bidirectional"))
      (node (ref "J4") (pin "G4") (pinfunction "GND_4_G4") (pintype "bidirectional"))
      (node (ref "J4") (pin "P6") (pinfunction "VSS_P6") (pintype "bidirectional"))
      (node (ref "MCP73831") (pin "2") (pinfunction "VSS_2") (pintype "power_in"))
      (node (ref "R1_PWRUSB1") (pin "1") (pinfunction "1_1") (pintype "passive"))
      (node (ref "R2") (pin "1") (pinfunction "1_1") (pintype "passive"))
      (node (ref "R2-USB") (pin "2") (pinfunction "2_2") (pintype "passive"))
      (node (ref "R2-USB1") (pin "1") (pinfunction "1_1") (pintype "passive"))
      (node (ref "R2_BAT") (pin "1") (pinfunction "1_1") (pintype "passive"))
      (node (ref "R4") (pin "1") (pinfunction "1_1") (pintype "passive"))
      (node (ref "RESET_BUTTON") (pin "1") (pinfunction "1_1") (pintype "passive"))
      (node (ref "RESET_BUTTON") (pin "2") (pinfunction "2_2") (pintype "passive"))
      (node (ref "SENSOR2") (pin "1") (pinfunction "GND_1") (pintype "power_in"))
      (node (ref "SENSOR2") (pin "5") (pinfunction "SDO_5") (pintype "bidirectional"))
      (node (ref "SENSOR2") (pin "7") (pinfunction "GND_7") (pintype "power_in"))
      (node (ref "SJ1") (pin "1") (pinfunction "1_1") (pintype "passive"))
      (node (ref "TANT") (pin "-") (pinfunction "-_-") (pintype "passive"))
      (node (ref "TP4") (pin "TP") (pinfunction "TP_TP") (pintype "input"))
      (node (ref "TP5") (pin "TP") (pinfunction "TP_TP") (pintype "input"))
      (node (ref "U1") (pin "4") (pinfunction "GND_4") (pintype "power_in"))
      (node (ref "U1") (pin "9") (pinfunction "EXP_9") (pintype "passive"))
      (node (ref "U2") (pin "1") (pinfunction "GND_1") (pintype "power_in"))
      (node (ref "U2") (pin "28") (pinfunction "GND_28") (pintype "power_in"))
      (node (ref "U2") (pin "29_1") (pinfunction "GND_29_1") (pintype "power_in"))
      (node (ref "U2") (pin "29_2") (pinfunction "GND_29_2") (pintype "power_in"))
      (node (ref "U2") (pin "29_3") (pinfunction "GND_29_3") (pintype "power_in"))
      (node (ref "U2") (pin "29_4") (pinfunction "GND_29_4") (pintype "power_in"))
      (node (ref "U2") (pin "29_5") (pinfunction "GND_29_5") (pintype "power_in"))
      (node (ref "U2") (pin "29_6") (pinfunction "GND_29_6") (pintype "power_in"))
      (node (ref "U2") (pin "29_7") (pinfunction "GND_29_7") (pintype "power_in"))
      (node (ref "U2") (pin "29_8") (pinfunction "GND_29_8") (pintype "power_in"))
      (node (ref "U2") (pin "29_9") (pinfunction "GND_29_9") (pintype "power_in"))
      (node (ref "U3") (pin "13") (pinfunction "GND_13") (pintype "power_in"))
      (node (ref "U4") (pin "1") (pinfunction "CTG_1") (pintype "power_in"))
      (node (ref "U4") (pin "4") (pinfunction "GND_4") (pintype "power_in"))
      (node (ref "U4") (pin "6") (pinfunction "QSTRT_6") (pintype "input"))
      (node (ref "U4") (pin "9") (pinfunction "EP_9") (pintype "power_in"))
    )
    (net (code "14") (name "GPIO8") (class "Default")
      (node (ref "R1") (pin "1") (pinfunction "1_1") (pintype "passive"))
      (node (ref "U2") (pin "10") (pinfunction "IO8_10") (pintype "bidirectional"))
    )
    (net (code "15") (name "I2C_PW") (class "Default")
      (node (ref "C1") (pin "1") (pinfunction "1_1") (pintype "passive"))
      (node (ref "C2") (pin "1") (pinfunction "1_1") (pintype "passive"))
      (node (ref "R1_PINH") (pin "2") (pinfunction "2_2") (pintype "passive"))
      (node (ref "R2_PINH") (pin "2") (pinfunction "2_2") (pintype "passive"))
      (node (ref "SENSOR2") (pin "2") (pinfunction "CSB_2") (pintype "input"))
      (node (ref "SENSOR2") (pin "6") (pinfunction "VDDIO_6") (pintype "power_in"))
      (node (ref "SENSOR2") (pin "8") (pinfunction "VDD_8") (pintype "power_in"))
      (node (ref "U2") (pin "17") (pinfunction "IO19_17") (pintype "bidirectional"))
    )
    (net (code "16") (name "INT_RTC") (class "Default")
      (node (ref "R1_PINH1") (pin "1") (pinfunction "1_1") (pintype "passive"))
      (node (ref "TP15") (pin "TP") (pinfunction "TP_TP") (pintype "input"))
      (node (ref "U2") (pin "8") (pinfunction "IO0_8") (pintype "bidirectional"))
      (node (ref "U3") (pin "3") (pinfunction "SQW/~{INT}_3") (pintype "output"))
    )
    (net (code "17") (name "IO{slash}BOOT") (class "Default")
      (node (ref "BOOT_BUTTON") (pin "3") (pinfunction "3_3") (pintype "passive"))
      (node (ref "BOOT_BUTTON") (pin "4") (pinfunction "4_4") (pintype "passive"))
      (node (ref "C6") (pin "1") (pinfunction "1_1") (pintype "passive"))
      (node (ref "R_BOOT") (pin "1") (pinfunction "1_1") (pintype "passive"))
      (node (ref "U2") (pin "15") (pinfunction "IO9_15") (pintype "bidirectional"))
    )
    (net (code "18") (name "IO{slash}CHANGE") (class "Default")
      (node (ref "C10") (pin "1") (pinfunction "1_1") (pintype "passive"))
      (node (ref "CHANGE_BUTTON") (pin "3") (pinfunction "3_3") (pintype "passive"))
      (node (ref "CHANGE_BUTTON") (pin "4") (pinfunction "4_4") (pintype "passive"))
      (node (ref "R_CHANGE") (pin "1") (pinfunction "1_1") (pintype "passive"))
      (node (ref "U2") (pin "23") (pinfunction "IO15_23") (pintype "bidirectional"))
    )
    (net (code "19") (name "MISO") (class "Default")
      (node (ref "D12") (pin "2") (pinfunction "2_2") (pintype "passive"))
      (node (ref "J4") (pin "P7") (pinfunction "DAT0_P7") (pintype "bidirectional"))
      (node (ref "R8") (pin "1") (pinfunction "1_1") (pintype "passive"))
      (node (ref "TP6") (pin "TP") (pinfunction "TP_TP") (pintype "input"))
      (node (ref "U1") (pin "2") (pinfunction "DO(IO1)_2") (pintype "bidirectional"))
      (node (ref "U2") (pin "27") (pinfunction "IO2_27") (pintype "bidirectional"))
    )
    (net (code "20") (name "MOSI") (class "Default")
      (node (ref "D11") (pin "2") (pinfunction "2_2") (pintype "passive"))
      (node (ref "J1") (pin "14") (pinfunction "14_14") (pintype "bidirectional"))
      (node (ref "J4") (pin "P3") (pinfunction "CMD_P3") (pintype "bidirectional"))
      (node (ref "R7") (pin "1") (pinfunction "1_1") (pintype "passive"))
      (node (ref "TP7") (pin "TP") (pinfunction "TP_TP") (pintype "input"))
      (node (ref "U1") (pin "5") (pinfunction "DI(IO0)_5") (pintype "bidirectional"))
      (node (ref "U2") (pin "7") (pinfunction "IO7_7") (pintype "bidirectional"))
    )
    (net (code "21") (name "Net-(CHG_LED-PadC)") (class "Default")
      (node (ref "CHG_LED") (pin "C") (pinfunction "C_C") (pintype "passive"))
      (node (ref "R1_BAT") (pin "1") (pinfunction "1_1") (pintype "passive"))
    )
    (net (code "22") (name "Net-(D2-CATHODE)") (class "Default")
      (node (ref "C1_BAT1") (pin "1") (pinfunction "1_1") (pintype "passive"))
      (node (ref "D2") (pin "1") (pinfunction "CATHODE_1") (pintype "bidirectional"))
      (node (ref "IC4") (pin "1") (pinfunction "VIN_1") (pintype "bidirectional"))
      (node (ref "IC4") (pin "3") (pinfunction "CE_3") (pintype "bidirectional"))
      (node (ref "Q1") (pin "2") (pinfunction "S_2") (pintype "bidirectional"))
    )
    (net (code "23") (name "Net-(D3-A)") (class "Default")
      (node (ref "C4") (pin "1") (pinfunction "1_1") (pintype "passive"))
      (node (ref "D3") (pin "2") (pinfunction "A_2") (pintype "bidirectional"))
      (node (ref "D4") (pin "1") (pinfunction "K_1") (pintype "bidirectional"))
    )
    (net (code "24") (name "Net-(D7-CATHODE)") (class "Default")
      (node (ref "D7") (pin "1") (pinfunction "CATHODE_1") (pintype "bidirectional"))
      (node (ref "R_CAPACITOR") (pin "1") (pinfunction "1_1") (pintype "passive"))
    )
    (net (code "25") (name "Net-(EFD_C1-Pad1)") (class "Default")
      (node (ref "EFD_C1") (pin "1") (pinfunction "1_1") (pintype "passive"))
      (node (ref "J1") (pin "4") (pinfunction "4_4") (pintype "bidirectional"))
    )
    (net (code "26") (name "Net-(EFD_C2-Pad1)") (class "Default")
      (node (ref "EFD_C2") (pin "1") (pinfunction "1_1") (pintype "passive"))
      (node (ref "J1") (pin "5") (pinfunction "5_5") (pintype "bidirectional"))
    )
    (net (code "27") (name "Net-(EFD_C6-Pad1)") (class "Default")
      (node (ref "EFD_C6") (pin "1") (pinfunction "1_1") (pintype "passive"))
      (node (ref "J1") (pin "18") (pinfunction "18_18") (pintype "bidirectional"))
    )
    (net (code "28") (name "Net-(EFD_C7-Pad1)") (class "Default")
      (node (ref "EFD_C7") (pin "1") (pinfunction "1_1") (pintype "passive"))
      (node (ref "J1") (pin "19") (pinfunction "19_19") (pintype "bidirectional"))
    )
    (net (code "29") (name "Net-(EPD_C8-Pad1)") (class "Default")
      (node (ref "EPD_C8") (pin "1") (pinfunction "1_1") (pintype "passive"))
      (node (ref "J1") (pin "20") (pinfunction "20_20") (pintype "bidirectional"))
    )
    (net (code "30") (name "Net-(EPD_C10-Pad1)") (class "Default")
      (node (ref "EPD_C10") (pin "1") (pinfunction "1_1") (pintype "passive"))
      (node (ref "J1") (pin "22") (pinfunction "22_22") (pintype "bidirectional"))
    )
    (net (code "31") (name "Net-(EPD_C12-Pad1)") (class "Default")
      (node (ref "EPD_C12") (pin "1") (pinfunction "1_1") (pintype "passive"))
      (node (ref "J1") (pin "24") (pinfunction "24_24") (pintype "bidirectional"))
    )
    (net (code "32") (name "Net-(IC1-CT)") (class "Default")
      (node (ref "C_DELAY") (pin "1") (pinfunction "1_1") (pintype "passive"))
      (node (ref "IC1") (pin "5") (pinfunction "CT_5") (pintype "bidirectional"))
    )
    (net (code "33") (name "Net-(J2-PadA5)") (class "Default")
      (node (ref "J2") (pin "A5") (pinfunction "A5_A5") (pintype "bidirectional"))
      (node (ref "R2-USB1") (pin "2") (pinfunction "2_2") (pintype "passive"))
    )
    (net (code "34") (name "Net-(J2-PadB5)") (class "Default")
      (node (ref "J2") (pin "B5") (pinfunction "B5_B5") (pintype "bidirectional"))
      (node (ref "R2-USB") (pin "1") (pinfunction "1_1") (pintype "passive"))
    )
    (net (code "35") (name "Net-(MCP73831-PROG)") (class "Default")
      (node (ref "MCP73831") (pin "5") (pinfunction "PROG_5") (pintype "input"))
      (node (ref "R2_BAT") (pin "2") (pinfunction "2_2") (pintype "passive"))
    )
    (net (code "36") (name "Net-(MCP73831-STAT)") (class "Default")
      (node (ref "MCP73831") (pin "1") (pinfunction "STAT_1") (pintype "output"))
      (node (ref "R1_BAT") (pin "2") (pinfunction "2_2") (pintype "passive"))
    )
    (net (code "37") (name "PREVGH") (class "Default")
      (node (ref "D5") (pin "1") (pinfunction "K_1") (pintype "bidirectional"))
      (node (ref "EPD_C9") (pin "1") (pinfunction "1_1") (pintype "passive"))
      (node (ref "J1") (pin "21") (pinfunction "21_21") (pintype "bidirectional"))
    )
    (net (code "38") (name "PREVGL") (class "Default")
      (node (ref "D4") (pin "2") (pinfunction "A_2") (pintype "bidirectional"))
      (node (ref "EPD_C11") (pin "1") (pinfunction "1_1") (pintype "passive"))
      (node (ref "J1") (pin "23") (pinfunction "23_23") (pintype "bidirectional"))
    )
    (net (code "39") (name "RESE") (class "Default")
      (node (ref "J1") (pin "3") (pinfunction "3_3") (pintype "bidirectional"))
      (node (ref "Q3") (pin "2") (pinfunction "S_2") (pintype "bidirectional"))
      (node (ref "R3") (pin "2") (pinfunction "2_2") (pintype "passive"))
    )
    (net (code "40") (name "RESE'") (class "Default")
      (node (ref "R2") (pin "2") (pinfunction "2_2") (pintype "passive"))
      (node (ref "R3") (pin "1") (pinfunction "1_1") (pintype "passive"))
      (node (ref "SJ1") (pin "2") (pinfunction "2_2") (pintype "passive"))
    )
    (net (code "41") (name "RESET") (class "Default")
      (node (ref "C5") (pin "1") (pinfunction "1_1") (pintype "passive"))
      (node (ref "IC1") (pin "1") (pinfunction "VOUT_1") (pintype "bidirectional"))
      (node (ref "RESET_BUTTON") (pin "3") (pinfunction "3_3") (pintype "passive"))
      (node (ref "RESET_BUTTON") (pin "4") (pinfunction "4_4") (pintype "passive"))
      (node (ref "R_RESET") (pin "1") (pinfunction "1_1") (pintype "passive"))
      (node (ref "U2") (pin "3") (pinfunction "EN_3") (pintype "input"))
    )
    (net (code "42") (name "RTC_RST") (class "Default")
      (node (ref "U2") (pin "16") (pinfunction "IO18_16") (pintype "bidirectional"))
      (node (ref "U3") (pin "4") (pinfunction "~{RST}_4") (pintype "input"))
    )
    (net (code "43") (name "RX") (class "Default")
      (node (ref "TP2") (pin "TP") (pinfunction "TP_TP") (pintype "input"))
      (node (ref "U2") (pin "24") (pinfunction "RXD0/GPIO17_24") (pintype "bidirectional"))
    )
    (net (code "44") (name "SCK") (class "Default")
      (node (ref "D10") (pin "2") (pinfunction "2_2") (pintype "passive"))
      (node (ref "J1") (pin "13") (pinfunction "13_13") (pintype "bidirectional"))
      (node (ref "J4") (pin "P5") (pinfunction "CLK_P5") (pintype "bidirectional"))
      (node (ref "R6") (pin "1") (pinfunction "1_1") (pintype "passive"))
      (node (ref "TP8") (pin "TP") (pinfunction "TP_TP") (pintype "input"))
      (node (ref "U1") (pin "6") (pinfunction "CLK_6") (pintype "input"))
      (node (ref "U2") (pin "6") (pinfunction "IO6_6") (pintype "bidirectional"))
    )
    (net (code "45") (name "SCL") (class "Default")
      (node (ref "J3") (pin "1") (pinfunction "1_1") (pintype "power_in"))
      (node (ref "R2_PINH") (pin "1") (pinfunction "1_1") (pintype "passive"))
      (node (ref "SENSOR2") (pin "4") (pinfunction "SCK_4") (pintype "input"))
      (node (ref "U2") (pin "20") (pinfunction "IO22_20") (pintype "bidirectional"))
      (node (ref "U3") (pin "16") (pinfunction "SCL_16") (pintype "input"))
      (node (ref "U4") (pin "7") (pinfunction "SCL_7") (pintype "input"))
    )
    (net (code "46") (name "SDA") (class "Default")
      (node (ref "J3") (pin "2") (pinfunction "2_2") (pintype "power_in"))
      (node (ref "R1_PINH") (pin "1") (pinfunction "1_1") (pintype "passive"))
      (node (ref "SENSOR2") (pin "3") (pinfunction "SDI_3") (pintype "bidirectional"))
      (node (ref "U2") (pin "19") (pinfunction "IO21_19") (pintype "bidirectional"))
      (node (ref "U3") (pin "15") (pinfunction "SDA_15") (pintype "bidirectional"))
      (node (ref "U4") (pin "8") (pinfunction "SDA_8") (pintype "bidirectional"))
    )
    (net (code "47") (name "SRC") (class "Default")
      (node (ref "C4") (pin "2") (pinfunction "2_2") (pintype "passive"))
      (node (ref "D5") (pin "2") (pinfunction "A_2") (pintype "bidirectional"))
      (node (ref "L1") (pin "1") (pinfunction "1_1") (pintype "passive"))
      (node (ref "Q3") (pin "3") (pinfunction "D_3") (pintype "bidirectional"))
    )
    (net (code "48") (name "SS_SD") (class "Default")
      (node (ref "D8") (pin "2") (pinfunction "2_2") (pintype "passive"))
      (node (ref "J4") (pin "P2") (pinfunction "CD/DAT3_P2") (pintype "bidirectional"))
      (node (ref "R10") (pin "1") (pinfunction "1_1") (pintype "passive"))
      (node (ref "U2") (pin "4") (pinfunction "IO4_4") (pintype "bidirectional"))
    )
    (net (code "49") (name "TX") (class "Default")
      (node (ref "TP1") (pin "TP") (pinfunction "TP_TP") (pintype "input"))
      (node (ref "U2") (pin "25") (pinfunction "TXD0/GPIO16_25") (pintype "bidirectional"))
    )
    (net (code "50") (name "USB_D+") (class "Default")
      (node (ref "D1") (pin "4") (pinfunction "I/O2_2_4") (pintype "bidirectional"))
      (node (ref "U2") (pin "14") (pinfunction "IO13_14") (pintype "bidirectional"))
    )
    (net (code "51") (name "USB_D-") (class "Default")
      (node (ref "D1") (pin "6") (pinfunction "I/O1_2_6") (pintype "bidirectional"))
      (node (ref "U2") (pin "13") (pinfunction "IO12_13") (pintype "bidirectional"))
    )
    (net (code "52") (name "VBAT") (class "Default")
      (node (ref "C2_BAT") (pin "1") (pinfunction "1_1") (pintype "passive"))
      (node (ref "MCP73831") (pin "3") (pinfunction "VBAT_3") (pintype "power_in"))
      (node (ref "Q1") (pin "3") (pinfunction "D_3") (pintype "bidirectional"))
      (node (ref "TP3") (pin "TP") (pinfunction "TP_TP") (pintype "input"))
      (node (ref "U4") (pin "2") (pinfunction "CELL_2") (pintype "power_in"))
      (node (ref "U4") (pin "3") (pinfunction "VDD_3") (pintype "power_in"))
    )
    (net (code "53") (name "VBUS") (class "Default")
      (node (ref "C1_BAT") (pin "1") (pinfunction "1_1") (pintype "passive"))
      (node (ref "C4_USB") (pin "1") (pinfunction "1_1") (pintype "passive"))
      (node (ref "C4_USB1") (pin "1") (pinfunction "1_1") (pintype "passive"))
      (node (ref "CHG_LED") (pin "A") (pinfunction "A_A") (pintype "passive"))
      (node (ref "D1") (pin "2") (pinfunction "GND_2") (pintype "bidirectional"))
      (node (ref "D2") (pin "2") (pinfunction "ANODE_2") (pintype "bidirectional"))
      (node (ref "MCP73831") (pin "4") (pinfunction "VIN_4") (pintype "power_in"))
      (node (ref "PFMF.050.1") (pin "2") (pinfunction "2_2") (pintype "passive"))
      (node (ref "Q1") (pin "1") (pinfunction "G_1") (pintype "bidirectional"))
      (node (ref "R1_PWRUSB1") (pin "2") (pinfunction "2_2") (pintype "passive"))
      (node (ref "TP14") (pin "TP") (pinfunction "TP_TP") (pintype "input"))
    )
    (net (code "54") (name "VRTC") (class "Default")
      (node (ref "C10_SUPERCAP") (pin "2") (pinfunction "2_2") (pintype "passive"))
      (node (ref "C8") (pin "1") (pinfunction "1_1") (pintype "passive"))
      (node (ref "R_CAPACITOR") (pin "2") (pinfunction "2_2") (pintype "passive"))
      (node (ref "U3") (pin "14") (pinfunction "VBAT_14") (pintype "power_in"))
    )
    (net (code "55") (name "VUSB") (class "Default")
      (node (ref "J2") (pin "A4") (pinfunction "A4_A4") (pintype "bidirectional"))
      (node (ref "J2") (pin "A9") (pinfunction "A9_A9") (pintype "bidirectional"))
      (node (ref "J2") (pin "B4") (pinfunction "B4_B4") (pintype "bidirectional"))
      (node (ref "J2") (pin "B9") (pinfunction "B9_B9") (pintype "bidirectional"))
      (node (ref "PFMF.050.1") (pin "1") (pinfunction "1_1") (pintype "passive"))
    )
    (net (code "56") (name "unconnected-(IC1-NC-Pad4)") (class "Default")
      (node (ref "IC1") (pin "4") (pinfunction "NC_4") (pintype "no_connect"))
    )
    (net (code "57") (name "unconnected-(IC4-NC-Pad4)") (class "Default")
      (node (ref "IC4") (pin "4") (pinfunction "NC_4") (pintype "no_connect"))
    )
    (net (code "58") (name "unconnected-(J1-Pad1)") (class "Default")
      (node (ref "J1") (pin "1") (pinfunction "1_1") (pintype "bidirectional"))
    )
    (net (code "59") (name "unconnected-(J1-Pad6)") (class "Default")
      (node (ref "J1") (pin "6") (pinfunction "6_6") (pintype "bidirectional"))
    )
    (net (code "60") (name "unconnected-(J1-Pad7)") (class "Default")
      (node (ref "J1") (pin "7") (pinfunction "7_7") (pintype "bidirectional"))
    )
    (net (code "61") (name "unconnected-(J2-PadA8)") (class "Default")
      (node (ref "J2") (pin "A8") (pinfunction "A8_A8") (pintype "bidirectional"))
    )
    (net (code "62") (name "unconnected-(J2-PadB8)") (class "Default")
      (node (ref "J2") (pin "B8") (pinfunction "B8_B8") (pintype "bidirectional"))
    )
    (net (code "63") (name "unconnected-(J4-DAT1-PadP8)") (class "Default")
      (node (ref "J4") (pin "P8") (pinfunction "DAT1_P8") (pintype "bidirectional"))
    )
    (net (code "64") (name "unconnected-(J4-DAT2-PadP1)") (class "Default")
      (node (ref "J4") (pin "P1") (pinfunction "DAT2_P1") (pintype "bidirectional"))
    )
    (net (code "65") (name "unconnected-(J4-DETECTION_1-PadS1)") (class "Default")
      (node (ref "J4") (pin "S1") (pinfunction "DETECTION_1_S1") (pintype "bidirectional"))
    )
    (net (code "66") (name "unconnected-(J4-DETECTION_2-PadS2)") (class "Default")
      (node (ref "J4") (pin "S2") (pinfunction "DETECTION_2_S2") (pintype "bidirectional"))
    )
    (net (code "67") (name "unconnected-(U2-NC-Pad22)") (class "Default")
      (node (ref "U2") (pin "22") (pinfunction "NC_22") (pintype "no_connect"))
    )
    (net (code "68") (name "unconnected-(U4-~{ALERT}-Pad5)") (class "Default")
      (node (ref "U4") (pin "5") (pinfunction "~{ALERT}_5") (pintype "output"))
    )
  )
)
